# RN42_breakout.net
KiCad netlist of a schematic drawn in EAGLE
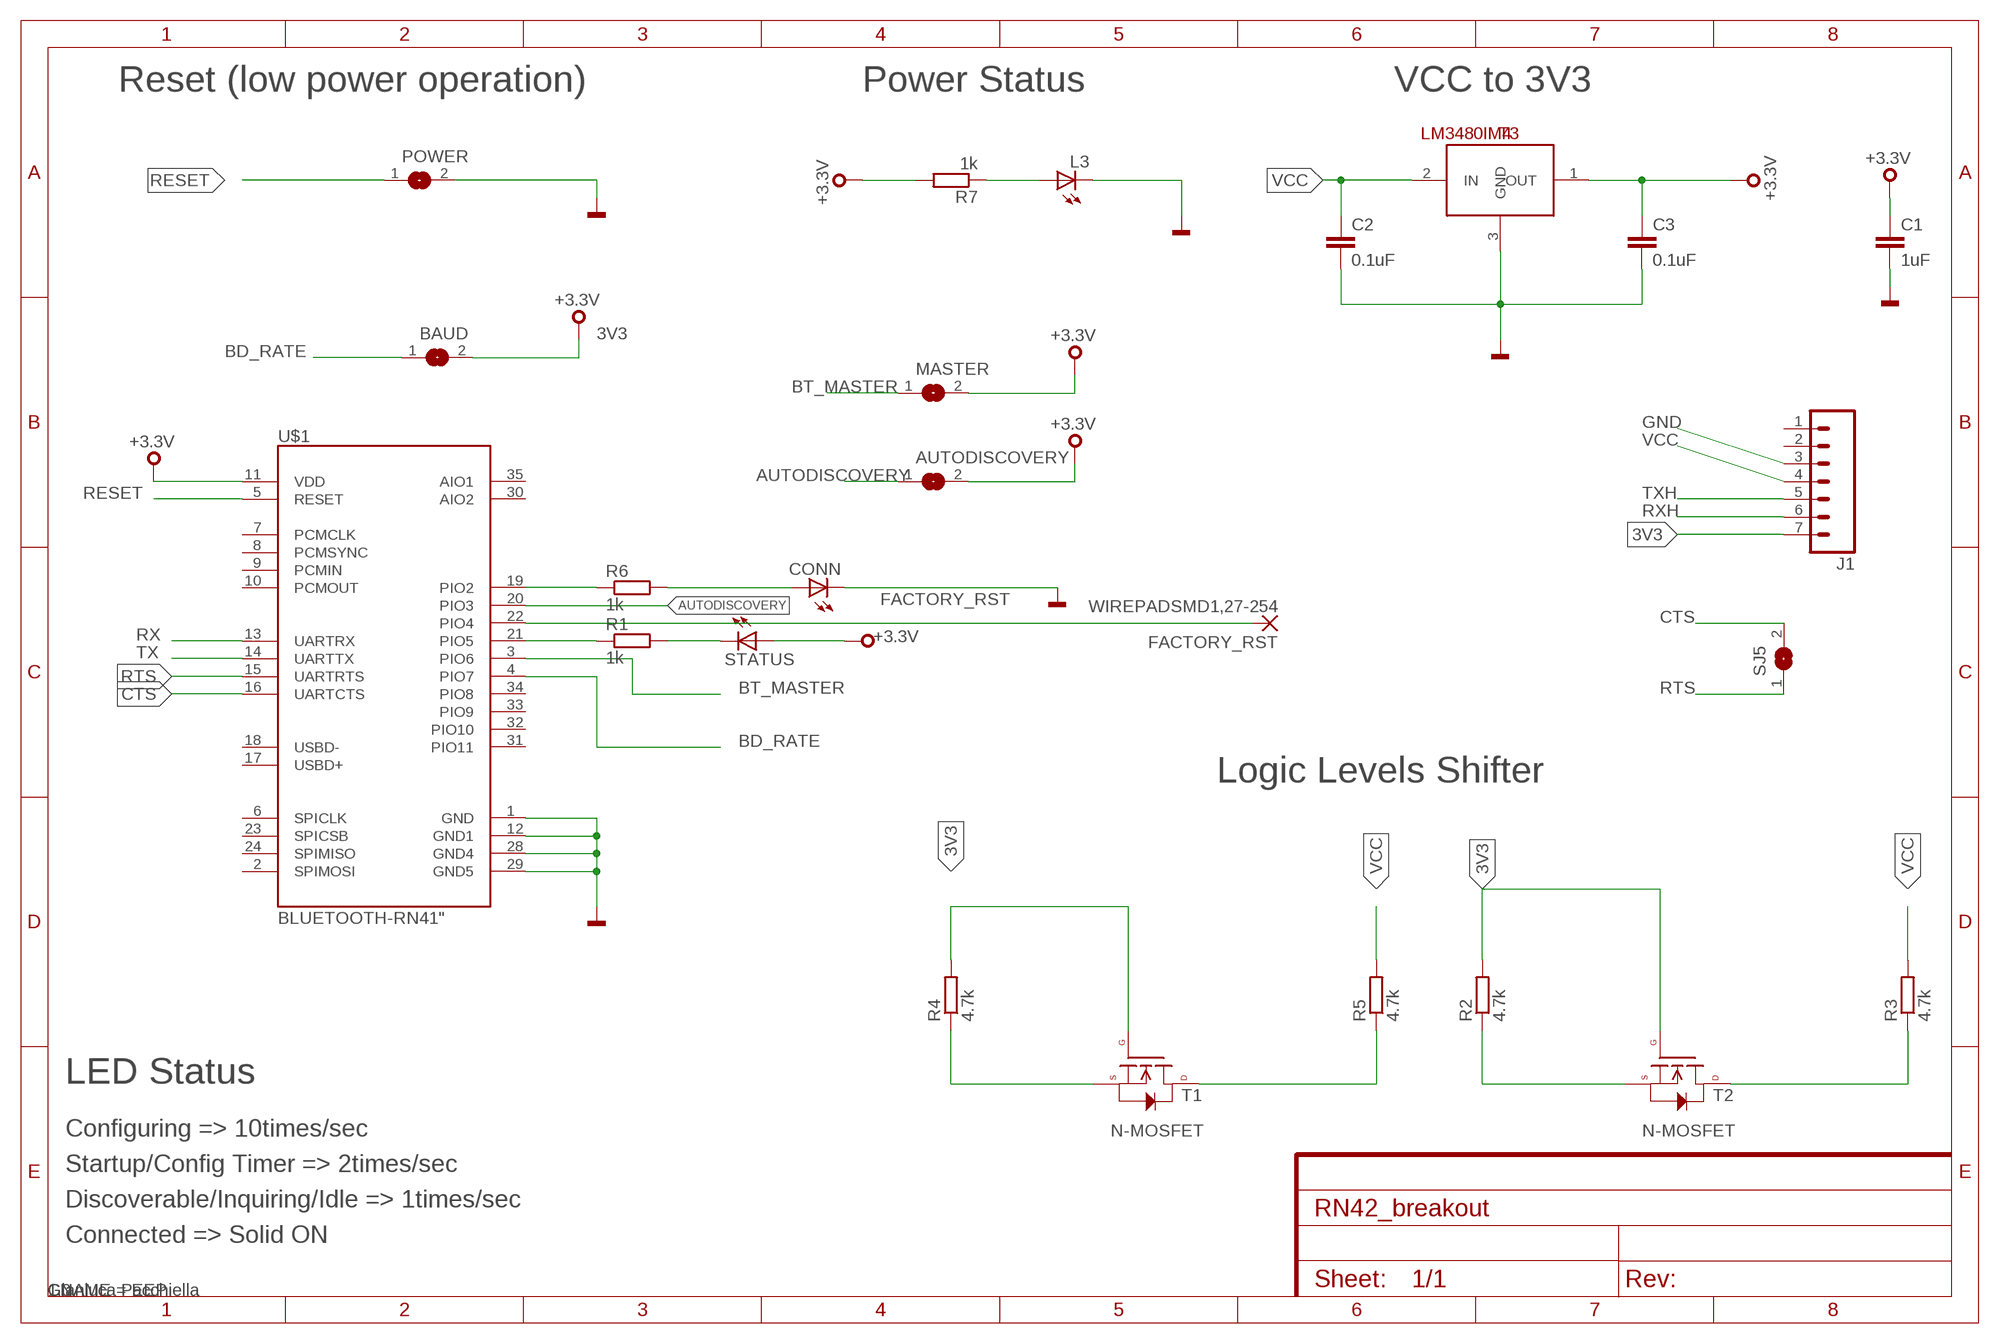
[diagram p0: schematic, sheet 1]

(export (version "E")
  (design (tool "Eeschema 10.0.6"))
  (components
    (comp (ref "AUTODISCOVERY")
      (value "SJ")
      (footprint "eagle-import:SJ")
      (libsource (lib "eagle-import") (part "SJ"))
    )
    (comp (ref "BAUD")
      (value "SJ")
      (footprint "eagle-import:SJ")
      (libsource (lib "eagle-import") (part "SJ"))
    )
    (comp (ref "C1")
      (value "1uF")
      (footprint "eagle-import:C0603")
      (libsource (lib "eagle-import") (part "C-EUC0603"))
    )
    (comp (ref "C2")
      (value "0.1uF")
      (footprint "eagle-import:0603-CAP")
      (libsource (lib "eagle-import") (part "CAP0603-CAP"))
    )
    (comp (ref "C3")
      (value "0.1uF")
      (footprint "eagle-import:0603-CAP")
      (libsource (lib "eagle-import") (part "CAP0603-CAP"))
    )
    (comp (ref "CONN")
      (value "LEDCHIPLED_0603")
      (footprint "eagle-import:CHIPLED_0603")
      (libsource (lib "eagle-import") (part "LEDCHIPLED_0603"))
    )
    (comp (ref "FACTORY_RST")
      (value "WIREPADSMD1,27-254")
      (footprint "eagle-import:SMD1,27-2,54")
      (libsource (lib "eagle-import") (part "WIREPADSMD1,27-254"))
    )
    (comp (ref "J1")
      (value "M07")
      (footprint "eagle-import:1X07")
      (libsource (lib "eagle-import") (part "M07"))
    )
    (comp (ref "L3")
      (value "LEDCHIPLED_0603")
      (footprint "eagle-import:CHIPLED_0603")
      (libsource (lib "eagle-import") (part "LEDCHIPLED_0603"))
    )
    (comp (ref "MASTER")
      (value "SJ")
      (footprint "eagle-import:SJ")
      (libsource (lib "eagle-import") (part "SJ"))
    )
    (comp (ref "POWER")
      (value "SJ")
      (footprint "eagle-import:SJ")
      (libsource (lib "eagle-import") (part "SJ"))
    )
    (comp (ref "R1")
      (value "1k")
      (footprint "eagle-import:R0603")
      (libsource (lib "eagle-import") (part "R-EU_R0603"))
    )
    (comp (ref "R2")
      (value "4.7k")
      (footprint "eagle-import:R0603")
      (libsource (lib "eagle-import") (part "R-EU_R0603"))
    )
    (comp (ref "R3")
      (value "4.7k")
      (footprint "eagle-import:R0603")
      (libsource (lib "eagle-import") (part "R-EU_R0603"))
    )
    (comp (ref "R4")
      (value "4.7k")
      (footprint "eagle-import:R0603")
      (libsource (lib "eagle-import") (part "R-EU_R0603"))
    )
    (comp (ref "R5")
      (value "4.7k")
      (footprint "eagle-import:R0603")
      (libsource (lib "eagle-import") (part "R-EU_R0603"))
    )
    (comp (ref "R6")
      (value "1k")
      (footprint "eagle-import:R0603")
      (libsource (lib "eagle-import") (part "R-EU_R0603"))
    )
    (comp (ref "R7")
      (value "1k")
      (footprint "eagle-import:R0603")
      (libsource (lib "eagle-import") (part "R-EU_R0603"))
    )
    (comp (ref "SJ5") (value "SJ") (footprint "eagle-import:SJ") (libsource (lib "eagle-import") (part "SJ")))
    (comp (ref "STATUS")
      (value "LEDCHIPLED_0603")
      (footprint "eagle-import:CHIPLED_0603")
      (libsource (lib "eagle-import") (part "LEDCHIPLED_0603"))
    )
    (comp (ref "T1")
      (value "N-MOSFET")
      (footprint "eagle-import:SOT23-3")
      (libsource (lib "eagle-import") (part "N-CHANNEL-MOSFET-BSS138"))
    )
    (comp (ref "T2")
      (value "N-MOSFET")
      (footprint "eagle-import:SOT23-3")
      (libsource (lib "eagle-import") (part "N-CHANNEL-MOSFET-BSS138"))
    )
    (comp (ref "T3")
      (value "LM3480IM4")
      (footprint "eagle-import:SOT23-3")
      (libsource (lib "eagle-import") (part "LM3480IM4"))
    )
    (comp (ref "U$1")
      (value "BLUETOOTH-RN41\"")
      (footprint "eagle-import:RN41")
      (libsource (lib "eagle-import") (part "BLUETOOTH-RN41{dblquote}"))
    )
  )
  (nets
    (net (code "1") (name "/BD_RATE") (class "Default")
      (node (ref "BAUD") (pin "1") (pinfunction "1_1") (pintype "passive"))
      (node (ref "U$1") (pin "4") (pinfunction "PIO7_4") (pintype "bidirectional"))
    )
    (net (code "2") (name "/BT_MASTER") (class "Default")
      (node (ref "MASTER") (pin "1") (pinfunction "1_1") (pintype "passive"))
      (node (ref "U$1") (pin "3") (pinfunction "PIO6_3") (pintype "bidirectional"))
    )
    (net (code "3") (name "/FACTORY_RST") (class "Default")
      (node (ref "FACTORY_RST") (pin "1") (pinfunction "P_1") (pintype "passive"))
      (node (ref "U$1") (pin "22") (pinfunction "PIO4_22") (pintype "bidirectional"))
    )
    (net (code "4") (name "/RX") (class "Default")
      (node (ref "R2") (pin "1") (pinfunction "1_1") (pintype "passive"))
      (node (ref "T2") (pin "2") (pinfunction "S_2") (pintype "passive"))
      (node (ref "U$1") (pin "13") (pinfunction "UARTRX_13") (pintype "bidirectional"))
    )
    (net (code "5") (name "/RXH") (class "Default")
      (node (ref "J1") (pin "6") (pinfunction "6_6") (pintype "passive"))
      (node (ref "R3") (pin "1") (pinfunction "1_1") (pintype "passive"))
      (node (ref "T2") (pin "3") (pinfunction "D_3") (pintype "passive"))
    )
    (net (code "6") (name "/TX") (class "Default")
      (node (ref "R4") (pin "1") (pinfunction "1_1") (pintype "passive"))
      (node (ref "T1") (pin "2") (pinfunction "S_2") (pintype "passive"))
      (node (ref "U$1") (pin "14") (pinfunction "UARTTX_14") (pintype "bidirectional"))
    )
    (net (code "7") (name "/TXH") (class "Default")
      (node (ref "J1") (pin "5") (pinfunction "5_5") (pintype "passive"))
      (node (ref "R5") (pin "1") (pinfunction "1_1") (pintype "passive"))
      (node (ref "T1") (pin "3") (pinfunction "D_3") (pintype "passive"))
    )
    (net (code "8") (name "3V3") (class "Default")
      (node (ref "AUTODISCOVERY") (pin "2") (pinfunction "2_2") (pintype "passive"))
      (node (ref "BAUD") (pin "2") (pinfunction "2_2") (pintype "passive"))
      (node (ref "C1") (pin "1") (pinfunction "1_1") (pintype "passive"))
      (node (ref "C3") (pin "1") (pinfunction "1_1") (pintype "passive"))
      (node (ref "J1") (pin "7") (pinfunction "7_7") (pintype "passive"))
      (node (ref "MASTER") (pin "2") (pinfunction "2_2") (pintype "passive"))
      (node (ref "R2") (pin "2") (pinfunction "2_2") (pintype "passive"))
      (node (ref "R4") (pin "2") (pinfunction "2_2") (pintype "passive"))
      (node (ref "R7") (pin "2") (pinfunction "2_2") (pintype "passive"))
      (node (ref "STATUS") (pin "A") (pinfunction "A_A") (pintype "passive"))
      (node (ref "T1") (pin "1") (pinfunction "G_1") (pintype "passive"))
      (node (ref "T2") (pin "1") (pinfunction "G_1") (pintype "passive"))
      (node (ref "T3") (pin "1") (pinfunction "OUT_1") (pintype "bidirectional"))
      (node (ref "U$1") (pin "11") (pinfunction "VDD_11") (pintype "bidirectional"))
    )
    (net (code "9") (name "AUTODISCOVERY") (class "Default")
      (node (ref "AUTODISCOVERY") (pin "1") (pinfunction "1_1") (pintype "passive"))
      (node (ref "U$1") (pin "20") (pinfunction "PIO3_20") (pintype "bidirectional"))
    )
    (net (code "10") (name "CTS") (class "Default")
      (node (ref "SJ5") (pin "2") (pinfunction "2_2") (pintype "passive"))
      (node (ref "U$1") (pin "16") (pinfunction "UARTCTS_16") (pintype "bidirectional"))
    )
    (net (code "11") (name "GND") (class "Default")
      (node (ref "C1") (pin "2") (pinfunction "2_2") (pintype "passive"))
      (node (ref "C2") (pin "2") (pinfunction "2_2") (pintype "passive"))
      (node (ref "C3") (pin "2") (pinfunction "2_2") (pintype "passive"))
      (node (ref "CONN") (pin "C") (pinfunction "C_C") (pintype "passive"))
      (node (ref "J1") (pin "3") (pinfunction "3_3") (pintype "passive"))
      (node (ref "L3") (pin "C") (pinfunction "C_C") (pintype "passive"))
      (node (ref "POWER") (pin "2") (pinfunction "2_2") (pintype "passive"))
      (node (ref "T3") (pin "3") (pinfunction "GND_3") (pintype "bidirectional"))
      (node (ref "U$1") (pin "1") (pinfunction "GND_1") (pintype "bidirectional"))
      (node (ref "U$1") (pin "12") (pinfunction "GND1_12") (pintype "bidirectional"))
      (node (ref "U$1") (pin "28") (pinfunction "GND4_28") (pintype "bidirectional"))
      (node (ref "U$1") (pin "29") (pinfunction "GND5_29") (pintype "bidirectional"))
    )
    (net (code "12") (name "Net-(CONN-PadA)") (class "Default")
      (node (ref "CONN") (pin "A") (pinfunction "A_A") (pintype "passive"))
      (node (ref "R6") (pin "2") (pinfunction "2_2") (pintype "passive"))
    )
    (net (code "13") (name "Net-(L3-PadA)") (class "Default")
      (node (ref "L3") (pin "A") (pinfunction "A_A") (pintype "passive"))
      (node (ref "R7") (pin "1") (pinfunction "1_1") (pintype "passive"))
    )
    (net (code "14") (name "Net-(R1-Pad2)") (class "Default")
      (node (ref "R1") (pin "2") (pinfunction "2_2") (pintype "passive"))
      (node (ref "STATUS") (pin "C") (pinfunction "C_C") (pintype "passive"))
    )
    (net (code "15") (name "Net-(U$1-PIO2)") (class "Default")
      (node (ref "R6") (pin "1") (pinfunction "1_1") (pintype "passive"))
      (node (ref "U$1") (pin "19") (pinfunction "PIO2_19") (pintype "bidirectional"))
    )
    (net (code "16") (name "Net-(U$1-PIO5)") (class "Default")
      (node (ref "R1") (pin "1") (pinfunction "1_1") (pintype "passive"))
      (node (ref "U$1") (pin "21") (pinfunction "PIO5_21") (pintype "bidirectional"))
    )
    (net (code "17") (name "RESET") (class "Default")
      (node (ref "POWER") (pin "1") (pinfunction "1_1") (pintype "passive"))
      (node (ref "U$1") (pin "5") (pinfunction "RESET_5") (pintype "bidirectional"))
    )
    (net (code "18") (name "RTS") (class "Default")
      (node (ref "SJ5") (pin "1") (pinfunction "1_1") (pintype "passive"))
      (node (ref "U$1") (pin "15") (pinfunction "UARTRTS_15") (pintype "bidirectional"))
    )
    (net (code "19") (name "VCC") (class "Default")
      (node (ref "C2") (pin "1") (pinfunction "1_1") (pintype "passive"))
      (node (ref "J1") (pin "4") (pinfunction "4_4") (pintype "passive"))
      (node (ref "R3") (pin "2") (pinfunction "2_2") (pintype "passive"))
      (node (ref "R5") (pin "2") (pinfunction "2_2") (pintype "passive"))
      (node (ref "T3") (pin "2") (pinfunction "IN_2") (pintype "bidirectional"))
    )
    (net (code "20") (name "unconnected-(J1-Pad1)") (class "Default")
      (node (ref "J1") (pin "1") (pinfunction "1_1") (pintype "passive"))
    )
    (net (code "21") (name "unconnected-(J1-Pad2)") (class "Default")
      (node (ref "J1") (pin "2") (pinfunction "2_2") (pintype "passive"))
    )
    (net (code "22") (name "unconnected-(U$1-AIO1-Pad35)") (class "Default")
      (node (ref "U$1") (pin "35") (pinfunction "AIO1_35") (pintype "bidirectional"))
    )
    (net (code "23") (name "unconnected-(U$1-AIO2-Pad30)") (class "Default")
      (node (ref "U$1") (pin "30") (pinfunction "AIO2_30") (pintype "bidirectional"))
    )
    (net (code "24") (name "unconnected-(U$1-PCMCLK-Pad7)") (class "Default")
      (node (ref "U$1") (pin "7") (pinfunction "PCMCLK_7") (pintype "bidirectional"))
    )
    (net (code "25") (name "unconnected-(U$1-PCMIN-Pad9)") (class "Default")
      (node (ref "U$1") (pin "9") (pinfunction "PCMIN_9") (pintype "bidirectional"))
    )
    (net (code "26") (name "unconnected-(U$1-PCMOUT-Pad10)") (class "Default")
      (node (ref "U$1") (pin "10") (pinfunction "PCMOUT_10") (pintype "bidirectional"))
    )
    (net (code "27") (name "unconnected-(U$1-PCMSYNC-Pad8)") (class "Default")
      (node (ref "U$1") (pin "8") (pinfunction "PCMSYNC_8") (pintype "bidirectional"))
    )
    (net (code "28") (name "unconnected-(U$1-PIO8-Pad34)") (class "Default")
      (node (ref "U$1") (pin "34") (pinfunction "PIO8_34") (pintype "bidirectional"))
    )
    (net (code "29") (name "unconnected-(U$1-PIO9-Pad33)") (class "Default")
      (node (ref "U$1") (pin "33") (pinfunction "PIO9_33") (pintype "bidirectional"))
    )
    (net (code "30") (name "unconnected-(U$1-PIO10-Pad32)") (class "Default")
      (node (ref "U$1") (pin "32") (pinfunction "PIO10_32") (pintype "bidirectional"))
    )
    (net (code "31") (name "unconnected-(U$1-PIO11-Pad31)") (class "Default")
      (node (ref "U$1") (pin "31") (pinfunction "PIO11_31") (pintype "bidirectional"))
    )
    (net (code "32") (name "unconnected-(U$1-SPICLK-Pad6)") (class "Default")
      (node (ref "U$1") (pin "6") (pinfunction "SPICLK_6") (pintype "bidirectional"))
    )
    (net (code "33") (name "unconnected-(U$1-SPICSB-Pad23)") (class "Default")
      (node (ref "U$1") (pin "23") (pinfunction "SPICSB_23") (pintype "bidirectional"))
    )
    (net (code "34") (name "unconnected-(U$1-SPIMISO-Pad24)") (class "Default")
      (node (ref "U$1") (pin "24") (pinfunction "SPIMISO_24") (pintype "bidirectional"))
    )
    (net (code "35") (name "unconnected-(U$1-SPIMOSI-Pad2)") (class "Default")
      (node (ref "U$1") (pin "2") (pinfunction "SPIMOSI_2") (pintype "bidirectional"))
    )
    (net (code "36") (name "unconnected-(U$1-USBD+-Pad17)") (class "Default")
      (node (ref "U$1") (pin "17") (pinfunction "USBD+_17") (pintype "bidirectional"))
    )
    (net (code "37") (name "unconnected-(U$1-USBD--Pad18)") (class "Default")
      (node (ref "U$1") (pin "18") (pinfunction "USBD-_18") (pintype "bidirectional"))
    )
  )
)
